# MotionClockSchematic.net
KiCad netlist of a schematic drawn in Altium Designer
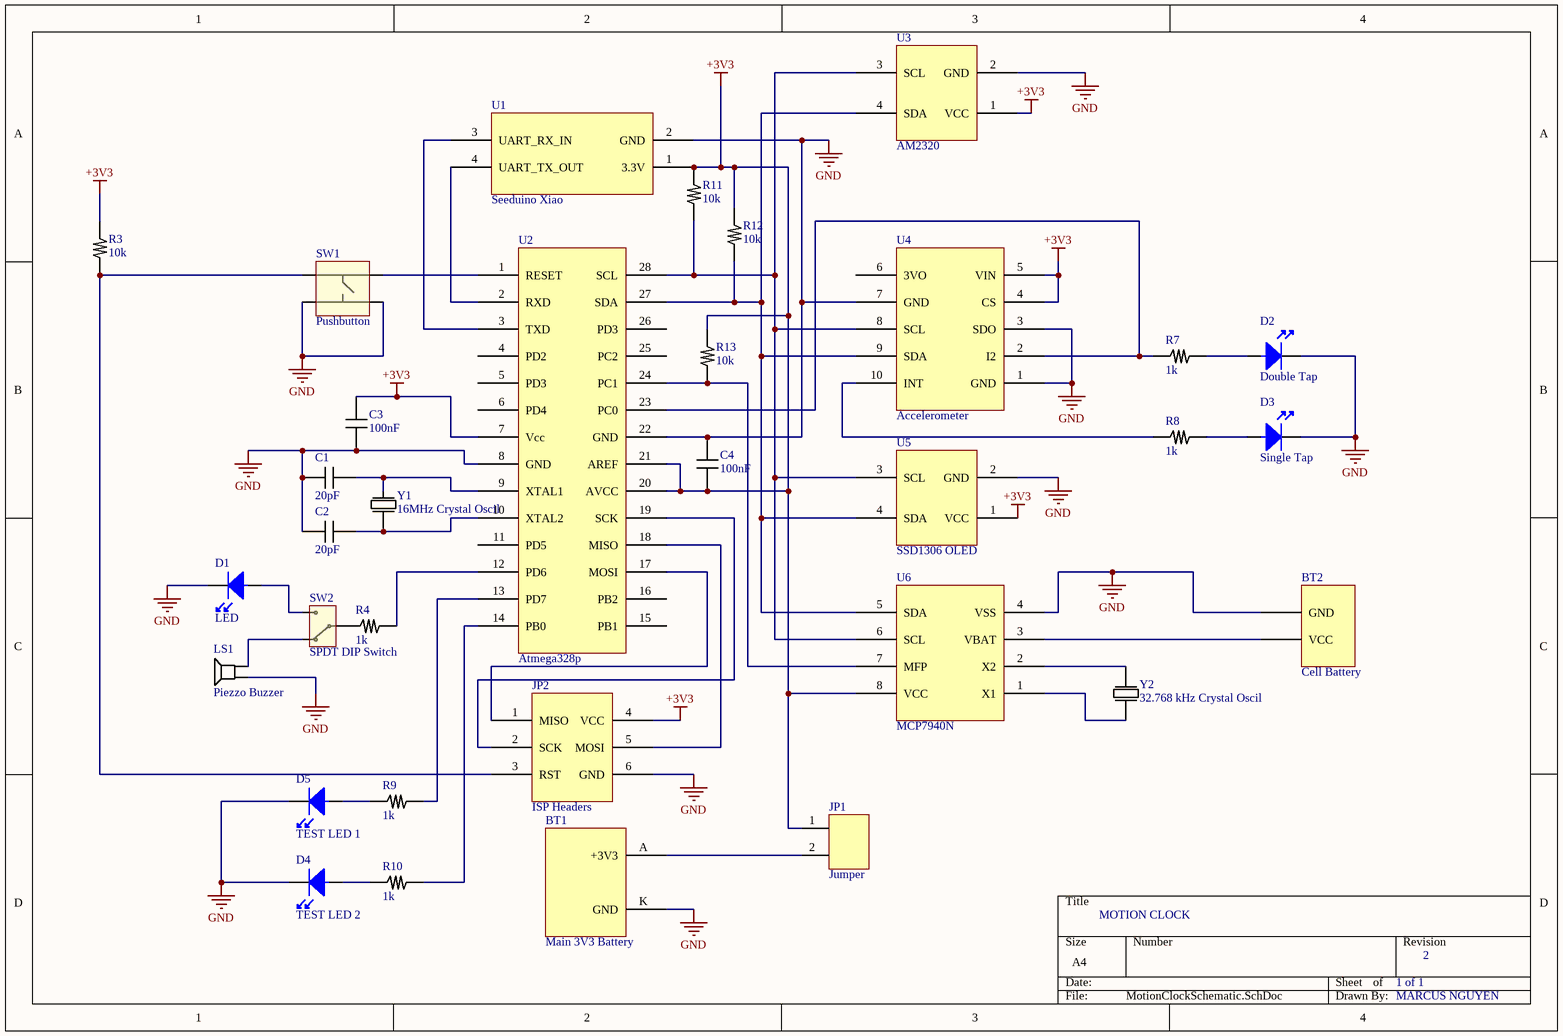
[diagram p0: MotionClockSchematic.SchDoc]

(export (version "E")
  (design (tool "Eeschema 10.0.6"))
  (components
    (comp (ref "BT1")
      (value "Main 3V3 Battery")
      (footprint "Main Battery Pins")
      (libsource (lib "SchematicLibrary") (part "Main 3V3 Battery"))
    )
    (comp (ref "BT2")
      (value "Cell Battery")
      (footprint "Cell Holder")
      (libsource (lib "SchematicLibrary") (part "Cell Battery"))
    )
    (comp (ref "C1")
      (value "20pF")
      (footprint "Capacitor")
      (libsource (lib "SchematicLibrary") (part "Capacitor"))
    )
    (comp (ref "C2")
      (value "20pF")
      (footprint "Capacitor")
      (libsource (lib "SchematicLibrary") (part "Capacitor"))
    )
    (comp (ref "C3")
      (value "100nF")
      (footprint "Capacitor")
      (libsource (lib "SchematicLibrary") (part "Capacitor"))
    )
    (comp (ref "C4")
      (value "100nF")
      (footprint "Capacitor")
      (libsource (lib "SchematicLibrary") (part "Capacitor"))
    )
    (comp (ref "D1") (value "LED") (footprint "LED") (libsource (lib "SchematicLibrary") (part "LED")))
    (comp (ref "D2") (value "Double Tap") (footprint "LED") (libsource (lib "SchematicLibrary") (part "LED")))
    (comp (ref "D3") (value "Single Tap") (footprint "LED") (libsource (lib "SchematicLibrary") (part "LED")))
    (comp (ref "D4") (value "TEST LED 2") (footprint "LED") (libsource (lib "SchematicLibrary") (part "LED")))
    (comp (ref "D5") (value "TEST LED 1") (footprint "LED") (libsource (lib "SchematicLibrary") (part "LED")))
    (comp (ref "JP1")
      (value "Jumper")
      (footprint "Jumper")
      (libsource (lib "SchematicLibrary") (part "Jumper"))
    )
    (comp (ref "JP2")
      (value "ISP Headers")
      (footprint "ISP Header")
      (libsource (lib "SchematicLibrary") (part "ISP Headers"))
    )
    (comp (ref "LS1")
      (value "Piezzo Buzzer")
      (footprint "Piezzo Buzzer v2")
      (libsource (lib "SchematicLibrary") (part "Piezzo Buzzer"))
    )
    (comp (ref "R3")
      (value "10k")
      (footprint "Resistor")
      (libsource (lib "SchematicLibrary") (part "10k Resistor"))
    )
    (comp (ref "R4")
      (value "1k")
      (footprint "Resistor")
      (libsource (lib "SchematicLibrary") (part "1k Resistor"))
    )
    (comp (ref "R7")
      (value "1k")
      (footprint "Resistor")
      (libsource (lib "SchematicLibrary") (part "1k Resistor"))
    )
    (comp (ref "R8")
      (value "1k")
      (footprint "Resistor")
      (libsource (lib "SchematicLibrary") (part "1k Resistor"))
    )
    (comp (ref "R9")
      (value "1k")
      (footprint "Resistor")
      (libsource (lib "SchematicLibrary") (part "1k Resistor"))
    )
    (comp (ref "R10")
      (value "1k")
      (footprint "Resistor")
      (libsource (lib "SchematicLibrary") (part "1k Resistor"))
    )
    (comp (ref "R11")
      (value "10k")
      (footprint "Resistor")
      (libsource (lib "SchematicLibrary") (part "10k Resistor"))
    )
    (comp (ref "R12")
      (value "10k")
      (footprint "Resistor")
      (libsource (lib "SchematicLibrary") (part "10k Resistor"))
    )
    (comp (ref "R13")
      (value "10k")
      (footprint "Resistor")
      (libsource (lib "SchematicLibrary") (part "10k Resistor"))
    )
    (comp (ref "SW1") (value "Pushbutton") (libsource (lib "SchematicLibrary") (part "Pushbutton")))
    (comp (ref "SW2")
      (value "SPDT DIP Switch")
      (footprint "SPDT")
      (libsource (lib "SchematicLibrary") (part "SPDT DIP Switch"))
    )
    (comp (ref "U1")
      (value "Seeduino Xiao")
      (footprint "Seeduino Xiao")
      (libsource (lib "SchematicLibrary") (part "Seeduino Xiao"))
    )
    (comp (ref "U2")
      (value "Atmega328p")
      (footprint "Atmega328p")
      (libsource (lib "SchematicLibrary") (part "Atmega328p"))
    )
    (comp (ref "U3")
      (value "AM2320")
      (footprint "AM2320")
      (libsource (lib "SchematicLibrary") (part "AM2320"))
    )
    (comp (ref "U4")
      (value "Accelerometer")
      (footprint "Accel")
      (libsource (lib "SchematicLibrary") (part "Accelerometer"))
    )
    (comp (ref "U5")
      (value "SSD1306 OLED")
      (footprint "SSD1306")
      (libsource (lib "SchematicLibrary") (part "SSD1306 OLED"))
    )
    (comp (ref "U6")
      (value "MCP7940N")
      (footprint "MCP7940N")
      (libsource (lib "SchematicLibrary") (part "MCP7940N"))
    )
    (comp (ref "Y1")
      (value "16MHz Crystal Oscil")
      (footprint "16MHz Crystal")
      (libsource (lib "SchematicLibrary") (part "16MHz Crystal Oscil"))
    )
    (comp (ref "Y2")
      (value "32.768 kHz Crystal Oscil")
      (footprint "32.768kHz")
      (libsource (lib "SchematicLibrary") (part "32.768 kHz Crystal Oscil"))
    )
  )
  (nets
    (net (code "1") (name "+3V3") (class "Default")
      (node (ref "C3") (pin "2") (pinfunction "2_2") (pintype "passive"))
      (node (ref "C4") (pin "1") (pinfunction "1_1") (pintype "passive"))
      (node (ref "JP1") (pin "1") (pinfunction "VCC_1") (pintype "passive"))
      (node (ref "JP2") (pin "4") (pinfunction "VCC_4") (pintype "passive"))
      (node (ref "R11") (pin "2") (pinfunction "2_2") (pintype "passive"))
      (node (ref "R12") (pin "2") (pinfunction "2_2") (pintype "passive"))
      (node (ref "R13") (pin "1") (pinfunction "1_1") (pintype "passive"))
      (node (ref "R3") (pin "1") (pinfunction "1_1") (pintype "passive"))
      (node (ref "U1") (pin "1") (pinfunction "3.3V_1") (pintype "passive"))
      (node (ref "U2") (pin "20") (pinfunction "AVCC_20") (pintype "passive"))
      (node (ref "U2") (pin "21") (pinfunction "AREF_21") (pintype "passive"))
      (node (ref "U2") (pin "7") (pinfunction "Vcc_7") (pintype "passive"))
      (node (ref "U3") (pin "1") (pinfunction "VCC_1") (pintype "passive"))
      (node (ref "U4") (pin "4") (pinfunction "CS_4") (pintype "passive"))
      (node (ref "U4") (pin "5") (pinfunction "VIN_5") (pintype "passive"))
      (node (ref "U5") (pin "1") (pinfunction "VCC_1") (pintype "passive"))
      (node (ref "U6") (pin "8") (pinfunction "VCC_8") (pintype "passive"))
    )
    (net (code "2") (name "GND") (class "Default")
      (node (ref "BT1") (pin "K") (pinfunction "GND_K") (pintype "passive"))
      (node (ref "BT2") (pin "K") (pinfunction "GND_K") (pintype "passive"))
      (node (ref "C1") (pin "1") (pinfunction "1_1") (pintype "passive"))
      (node (ref "C2") (pin "2") (pinfunction "2_2") (pintype "passive"))
      (node (ref "C3") (pin "1") (pinfunction "1_1") (pintype "passive"))
      (node (ref "C4") (pin "2") (pinfunction "2_2") (pintype "passive"))
      (node (ref "D1") (pin "K") (pinfunction "K_K") (pintype "passive"))
      (node (ref "D2") (pin "K") (pinfunction "K_K") (pintype "passive"))
      (node (ref "D3") (pin "K") (pinfunction "K_K") (pintype "passive"))
      (node (ref "D4") (pin "K") (pinfunction "K_K") (pintype "passive"))
      (node (ref "D5") (pin "K") (pinfunction "K_K") (pintype "passive"))
      (node (ref "JP2") (pin "6") (pinfunction "GND_6") (pintype "passive"))
      (node (ref "LS1") (pin "K") (pinfunction "K_K") (pintype "passive"))
      (node (ref "SW1") (pin "2") (pinfunction "2_2") (pintype "passive"))
      (node (ref "SW1") (pin "4") (pinfunction "4_4") (pintype "passive"))
      (node (ref "U1") (pin "2") (pinfunction "GND_2") (pintype "passive"))
      (node (ref "U2") (pin "22") (pinfunction "GND_22") (pintype "passive"))
      (node (ref "U2") (pin "8") (pinfunction "GND_8") (pintype "passive"))
      (node (ref "U3") (pin "2") (pinfunction "GND_2") (pintype "passive"))
      (node (ref "U4") (pin "1") (pinfunction "GND_1") (pintype "passive"))
      (node (ref "U4") (pin "3") (pinfunction "SDO_3") (pintype "passive"))
      (node (ref "U4") (pin "7") (pinfunction "GND_7") (pintype "passive"))
      (node (ref "U5") (pin "2") (pinfunction "GND_2") (pintype "passive"))
      (node (ref "U6") (pin "4") (pinfunction "VSS_4") (pintype "passive"))
    )
    (net (code "3") (name "Net-(BT1-+3V3)") (class "Default")
      (node (ref "BT1") (pin "A") (pinfunction "+3V3_A") (pintype "passive"))
      (node (ref "JP1") (pin "2") (pinfunction "GND_2") (pintype "passive"))
    )
    (net (code "4") (name "Net-(BT2-VCC)") (class "Default")
      (node (ref "BT2") (pin "A") (pinfunction "VCC_A") (pintype "passive"))
      (node (ref "U6") (pin "3") (pinfunction "VBAT_3") (pintype "passive"))
    )
    (net (code "5") (name "Net-(D1-PadA)") (class "Default")
      (node (ref "D1") (pin "A") (pinfunction "A_A") (pintype "passive"))
      (node (ref "SW2") (pin "3") (pinfunction "3_3") (pintype "passive"))
    )
    (net (code "6") (name "Net-(D2-PadA)") (class "Default")
      (node (ref "D2") (pin "A") (pinfunction "A_A") (pintype "passive"))
      (node (ref "R7") (pin "2") (pinfunction "2_2") (pintype "passive"))
    )
    (net (code "7") (name "Net-(D3-PadA)") (class "Default")
      (node (ref "D3") (pin "A") (pinfunction "A_A") (pintype "passive"))
      (node (ref "R8") (pin "2") (pinfunction "2_2") (pintype "passive"))
    )
    (net (code "8") (name "Net-(D4-PadA)") (class "Default")
      (node (ref "D4") (pin "A") (pinfunction "A_A") (pintype "passive"))
      (node (ref "R10") (pin "1") (pinfunction "1_1") (pintype "passive"))
    )
    (net (code "9") (name "Net-(D5-PadA)") (class "Default")
      (node (ref "D5") (pin "A") (pinfunction "A_A") (pintype "passive"))
      (node (ref "R9") (pin "1") (pinfunction "1_1") (pintype "passive"))
    )
    (net (code "10") (name "Net-(JP2-MISO)") (class "Default")
      (node (ref "JP2") (pin "1") (pinfunction "MISO_1") (pintype "passive"))
      (node (ref "U2") (pin "17") (pinfunction "MOSI_17") (pintype "passive"))
    )
    (net (code "11") (name "Net-(JP2-MOSI)") (class "Default")
      (node (ref "JP2") (pin "5") (pinfunction "MOSI_5") (pintype "passive"))
      (node (ref "U2") (pin "18") (pinfunction "MISO_18") (pintype "passive"))
    )
    (net (code "12") (name "Net-(JP2-RST)") (class "Default")
      (node (ref "JP2") (pin "3") (pinfunction "RST_3") (pintype "passive"))
      (node (ref "R3") (pin "2") (pinfunction "2_2") (pintype "passive"))
      (node (ref "SW1") (pin "1") (pinfunction "1_1") (pintype "passive"))
    )
    (net (code "13") (name "Net-(JP2-SCK)") (class "Default")
      (node (ref "JP2") (pin "2") (pinfunction "SCK_2") (pintype "passive"))
      (node (ref "U2") (pin "19") (pinfunction "SCK_19") (pintype "passive"))
    )
    (net (code "14") (name "Net-(LS1-PadA)") (class "Default")
      (node (ref "LS1") (pin "A") (pinfunction "A_A") (pintype "passive"))
      (node (ref "SW2") (pin "2") (pinfunction "2_2") (pintype "passive"))
    )
    (net (code "15") (name "Net-(R4-Pad1)") (class "Default")
      (node (ref "R4") (pin "1") (pinfunction "1_1") (pintype "passive"))
      (node (ref "SW2") (pin "1") (pinfunction "1_1") (pintype "passive"))
    )
    (net (code "16") (name "Net-(U1-UART_RX_IN)") (class "Default")
      (node (ref "U1") (pin "3") (pinfunction "UART_RX_IN_3") (pintype "passive"))
      (node (ref "U2") (pin "3") (pinfunction "TXD_3") (pintype "passive"))
    )
    (net (code "17") (name "Net-(U1-UART_TX_OUT)") (class "Default")
      (node (ref "U1") (pin "4") (pinfunction "UART_TX_OUT_4") (pintype "passive"))
      (node (ref "U2") (pin "2") (pinfunction "RXD_2") (pintype "passive"))
    )
    (net (code "18") (name "Net-(U2-PB0)") (class "Default")
      (node (ref "R10") (pin "2") (pinfunction "2_2") (pintype "passive"))
      (node (ref "U2") (pin "14") (pinfunction "PB0_14") (pintype "passive"))
    )
    (net (code "19") (name "Net-(U2-PC0)") (class "Default")
      (node (ref "R7") (pin "1") (pinfunction "1_1") (pintype "passive"))
      (node (ref "U2") (pin "23") (pinfunction "PC0_23") (pintype "passive"))
      (node (ref "U4") (pin "2") (pinfunction "I2_2") (pintype "passive"))
    )
    (net (code "20") (name "Net-(U2-PC1)") (class "Default")
      (node (ref "R13") (pin "2") (pinfunction "2_2") (pintype "passive"))
      (node (ref "U2") (pin "24") (pinfunction "PC1_24") (pintype "passive"))
      (node (ref "U6") (pin "7") (pinfunction "MFP_7") (pintype "passive"))
    )
    (net (code "21") (name "Net-(U2-PD6)") (class "Default")
      (node (ref "R4") (pin "2") (pinfunction "2_2") (pintype "passive"))
      (node (ref "U2") (pin "12") (pinfunction "PD6_12") (pintype "passive"))
    )
    (net (code "22") (name "Net-(U2-PD7)") (class "Default")
      (node (ref "R9") (pin "2") (pinfunction "2_2") (pintype "passive"))
      (node (ref "U2") (pin "13") (pinfunction "PD7_13") (pintype "passive"))
    )
    (net (code "23") (name "Net-(U2-RESET)") (class "Default")
      (node (ref "SW1") (pin "3") (pinfunction "3_3") (pintype "passive"))
      (node (ref "U2") (pin "1") (pinfunction "RESET_1") (pintype "passive"))
    )
    (net (code "24") (name "Net-(U2-SCL)") (class "Default")
      (node (ref "R11") (pin "1") (pinfunction "1_1") (pintype "passive"))
      (node (ref "U2") (pin "28") (pinfunction "SCL_28") (pintype "passive"))
      (node (ref "U3") (pin "3") (pinfunction "SCL_3") (pintype "passive"))
      (node (ref "U4") (pin "8") (pinfunction "SCL_8") (pintype "passive"))
      (node (ref "U5") (pin "3") (pinfunction "SCL_3") (pintype "passive"))
      (node (ref "U6") (pin "6") (pinfunction "SCL_6") (pintype "passive"))
    )
    (net (code "25") (name "Net-(U2-SDA)") (class "Default")
      (node (ref "R12") (pin "1") (pinfunction "1_1") (pintype "passive"))
      (node (ref "U2") (pin "27") (pinfunction "SDA_27") (pintype "passive"))
      (node (ref "U3") (pin "4") (pinfunction "SDA_4") (pintype "passive"))
      (node (ref "U4") (pin "9") (pinfunction "SDA_9") (pintype "passive"))
      (node (ref "U5") (pin "4") (pinfunction "SDA_4") (pintype "passive"))
      (node (ref "U6") (pin "5") (pinfunction "SDA_5") (pintype "passive"))
    )
    (net (code "26") (name "Net-(U2-XTAL1)") (class "Default")
      (node (ref "C1") (pin "2") (pinfunction "2_2") (pintype "passive"))
      (node (ref "U2") (pin "9") (pinfunction "XTAL1_9") (pintype "passive"))
      (node (ref "Y1") (pin "2") (pinfunction "2_2") (pintype "passive"))
    )
    (net (code "27") (name "Net-(U2-XTAL2)") (class "Default")
      (node (ref "C2") (pin "1") (pinfunction "1_1") (pintype "passive"))
      (node (ref "U2") (pin "10") (pinfunction "XTAL2_10") (pintype "passive"))
      (node (ref "Y1") (pin "1") (pinfunction "1_1") (pintype "passive"))
    )
    (net (code "28") (name "Net-(U4-INT)") (class "Default")
      (node (ref "R8") (pin "1") (pinfunction "1_1") (pintype "passive"))
      (node (ref "U4") (pin "10") (pinfunction "INT_10") (pintype "passive"))
    )
    (net (code "29") (name "Net-(U6-X1)") (class "Default")
      (node (ref "U6") (pin "1") (pinfunction "X1_1") (pintype "passive"))
      (node (ref "Y2") (pin "1") (pinfunction "1_1") (pintype "passive"))
    )
    (net (code "30") (name "Net-(U6-X2)") (class "Default")
      (node (ref "U6") (pin "2") (pinfunction "X2_2") (pintype "passive"))
      (node (ref "Y2") (pin "2") (pinfunction "2_2") (pintype "passive"))
    )
    (net (code "31") (name "unconnected-(U2-PB1-Pad15)") (class "Default")
      (node (ref "U2") (pin "15") (pinfunction "PB1_15") (pintype "passive"))
    )
    (net (code "32") (name "unconnected-(U2-PB2-Pad16)") (class "Default")
      (node (ref "U2") (pin "16") (pinfunction "PB2_16") (pintype "passive"))
    )
    (net (code "33") (name "unconnected-(U2-PC2-Pad25)") (class "Default")
      (node (ref "U2") (pin "25") (pinfunction "PC2_25") (pintype "passive"))
    )
    (net (code "34") (name "unconnected-(U2-PD2-Pad4)") (class "Default")
      (node (ref "U2") (pin "4") (pinfunction "PD2_4") (pintype "passive"))
    )
    (net (code "35") (name "unconnected-(U2-PD3-Pad5)") (class "Default")
      (node (ref "U2") (pin "5") (pinfunction "PD3_5") (pintype "passive"))
    )
    (net (code "36") (name "unconnected-(U2-PD3-Pad26)") (class "Default")
      (node (ref "U2") (pin "26") (pinfunction "PD3_26") (pintype "passive"))
    )
    (net (code "37") (name "unconnected-(U2-PD4-Pad6)") (class "Default")
      (node (ref "U2") (pin "6") (pinfunction "PD4_6") (pintype "passive"))
    )
    (net (code "38") (name "unconnected-(U2-PD5-Pad11)") (class "Default")
      (node (ref "U2") (pin "11") (pinfunction "PD5_11") (pintype "passive"))
    )
    (net (code "39") (name "unconnected-(U4-3VO-Pad6)") (class "Default")
      (node (ref "U4") (pin "6") (pinfunction "3VO_6") (pintype "passive"))
    )
  )
)
